# YOTSUBA_AP_EM_ver_3_1.net
KiCad netlist of a schematic drawn in EAGLE
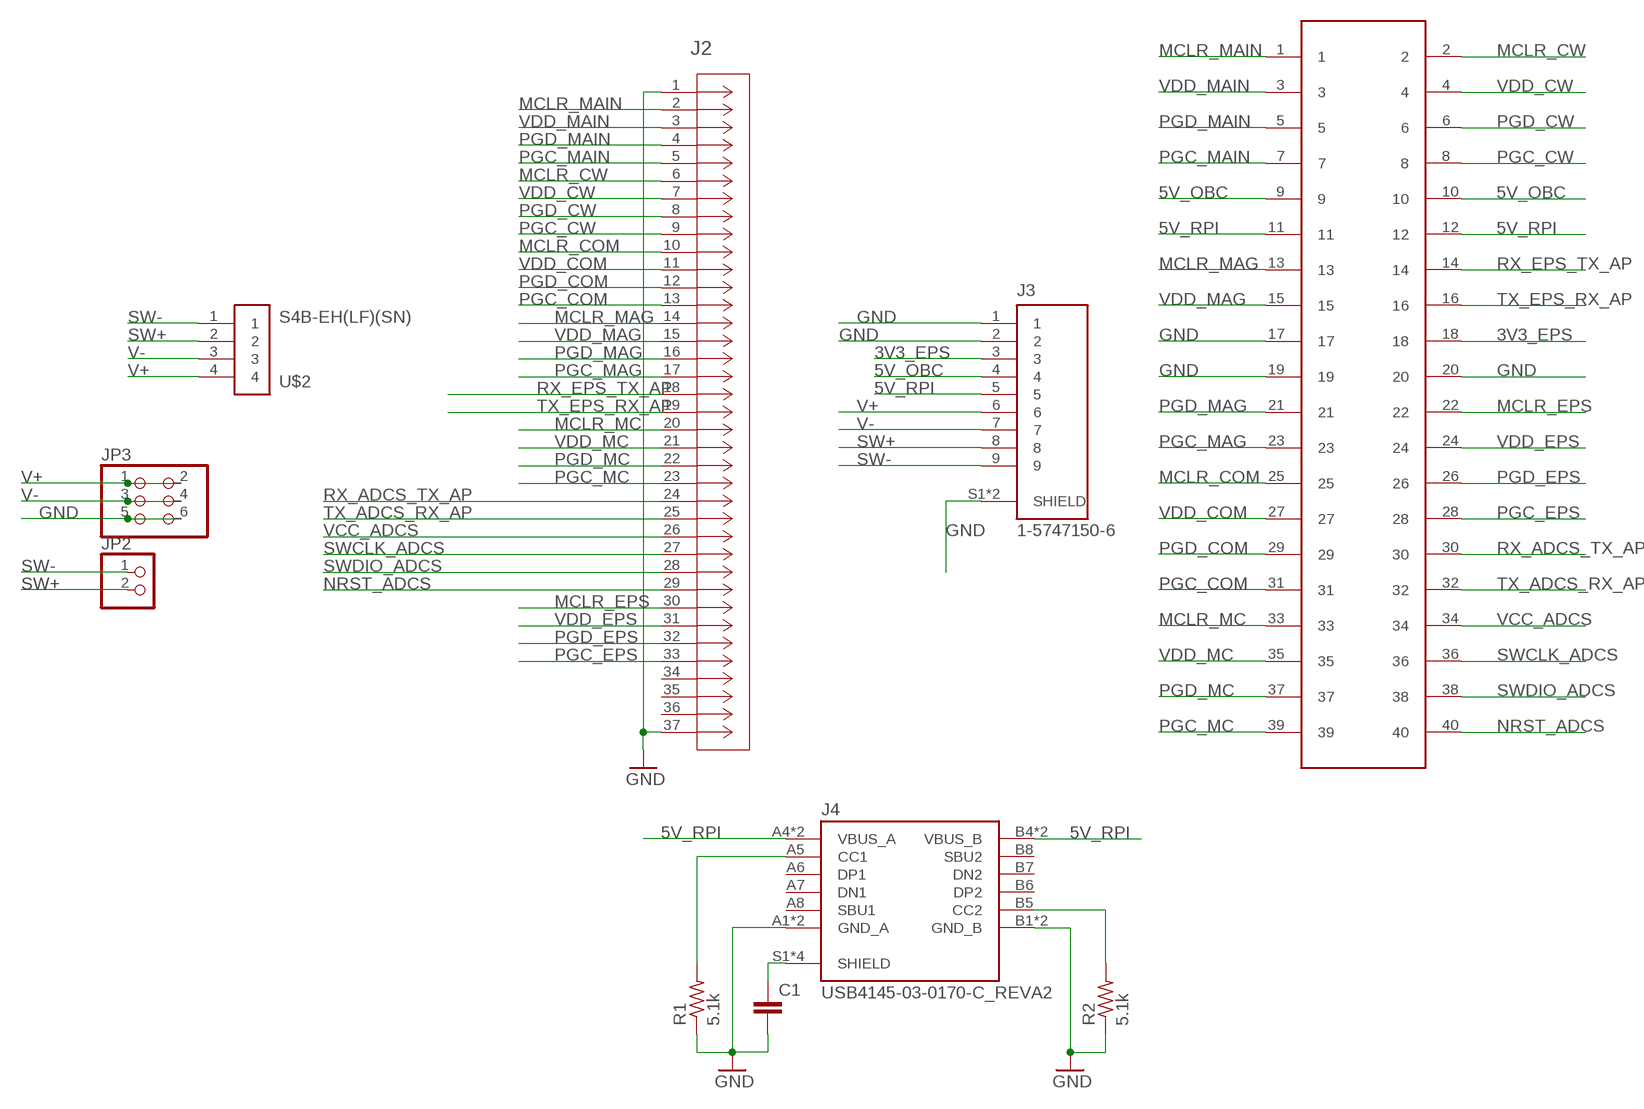
[diagram p0: schematic, sheet 1]

(export (version "E")
  (design (tool "Eeschema 10.0.6"))
  (components
    (comp (ref "C1")
      (value "C-EUC2012")
      (footprint "eagle-import:C2012")
      (libsource (lib "eagle-import") (part "C-EUC2012"))
    )
    (comp (ref "J2")
      (value "1-5747301-6")
      (footprint "eagle-import:CONN_1-5747301-6_TYC")
      (fields (field (name "COPYRIGHT") "Copyright (C) 2023 Ultra Librarian. All rights reserved."))
      (libsource (lib "eagle-import") (part "1-5747301-6"))
    )
    (comp (ref "J3")
      (value "1-5747150-6")
      (footprint "eagle-import:TE_1-5747150-6")
      (fields (field (name "MF") "TE Connectivity"))
      (libsource (lib "eagle-import") (part "1-5747150-6"))
    )
    (comp (ref "J4")
      (value "USB4145-03-0170-C_REVA2")
      (footprint "eagle-import:GCT_USB4145-03-0170-C_REVA2")
      (fields (field (name "MF") "Global Connector Technology") (field (name "MP") "USB4145-03-0170-C"))
      (libsource (lib "eagle-import") (part "USB4145-03-0170-C_REVA2"))
    )
    (comp (ref "JP2")
      (value "PINHD-1X2")
      (footprint "eagle-import:1X02")
      (libsource (lib "eagle-import") (part "PINHD-1X2"))
    )
    (comp (ref "JP3")
      (value "PINHD-2X3")
      (footprint "eagle-import:2X03")
      (libsource (lib "eagle-import") (part "PINHD-2X3"))
    )
    (comp (ref "R1")
      (value "5.1k")
      (footprint "eagle-import:R0805")
      (libsource (lib "eagle-import") (part "R-US_R0805"))
    )
    (comp (ref "R2")
      (value "5.1k")
      (footprint "eagle-import:R0805")
      (libsource (lib "eagle-import") (part "R-US_R0805"))
    )
    (comp (ref "U$1")
      (value "M50-3902042")
      (footprint "eagle-import:M50-3902042")
      (libsource (lib "eagle-import") (part "M50-3902042"))
    )
    (comp (ref "U$2")
      (value "S4B-EH(LF)(SN)")
      (footprint "eagle-import:JST_S4B-EH(LF)(SN)")
      (fields (field (name "MF") "JST Sales"))
      (libsource (lib "eagle-import") (part "S4B-EH(LF)(SN)"))
    )
  )
  (nets
    (net (code "1") (name "/3V3_EPS") (class "Default")
      (node (ref "J3") (pin "3") (pinfunction "3_3") (pintype "passive"))
      (node (ref "U$1") (pin "18") (pinfunction "18_18") (pintype "bidirectional"))
    )
    (net (code "2") (name "/5V_OBC") (class "Default")
      (node (ref "J3") (pin "4") (pinfunction "4_4") (pintype "passive"))
      (node (ref "U$1") (pin "10") (pinfunction "10_10") (pintype "bidirectional"))
      (node (ref "U$1") (pin "9") (pinfunction "9_9") (pintype "bidirectional"))
    )
    (net (code "3") (name "/5V_RPI") (class "Default")
      (node (ref "J3") (pin "5") (pinfunction "5_5") (pintype "passive"))
      (node (ref "J4") (pin "A4") (pinfunction "VBUS_A_A4") (pintype "power_in"))
      (node (ref "J4") (pin "A9") (pinfunction "VBUS_A_A9") (pintype "power_in"))
      (node (ref "J4") (pin "B4") (pinfunction "VBUS_B_B4") (pintype "power_in"))
      (node (ref "J4") (pin "B9") (pinfunction "VBUS_B_B9") (pintype "power_in"))
      (node (ref "U$1") (pin "11") (pinfunction "11_11") (pintype "bidirectional"))
      (node (ref "U$1") (pin "12") (pinfunction "12_12") (pintype "bidirectional"))
    )
    (net (code "4") (name "/MCLR_COM") (class "Default")
      (node (ref "J2") (pin "10") (pinfunction "10_10") (pintype "passive"))
      (node (ref "U$1") (pin "25") (pinfunction "25_25") (pintype "bidirectional"))
    )
    (net (code "5") (name "/MCLR_CW") (class "Default")
      (node (ref "J2") (pin "6") (pinfunction "6_6") (pintype "passive"))
      (node (ref "U$1") (pin "2") (pinfunction "2_2") (pintype "bidirectional"))
    )
    (net (code "6") (name "/MCLR_EPS") (class "Default")
      (node (ref "J2") (pin "30") (pinfunction "30_30") (pintype "passive"))
      (node (ref "U$1") (pin "22") (pinfunction "22_22") (pintype "bidirectional"))
    )
    (net (code "7") (name "/MCLR_MAG") (class "Default")
      (node (ref "J2") (pin "14") (pinfunction "14_14") (pintype "passive"))
      (node (ref "U$1") (pin "13") (pinfunction "13_13") (pintype "bidirectional"))
    )
    (net (code "8") (name "/MCLR_MAIN") (class "Default")
      (node (ref "J2") (pin "2") (pinfunction "2_2") (pintype "passive"))
      (node (ref "U$1") (pin "1") (pinfunction "1_1") (pintype "bidirectional"))
    )
    (net (code "9") (name "/MCLR_MC") (class "Default")
      (node (ref "J2") (pin "20") (pinfunction "20_20") (pintype "passive"))
      (node (ref "U$1") (pin "33") (pinfunction "33_33") (pintype "bidirectional"))
    )
    (net (code "10") (name "/NRST_ADCS") (class "Default")
      (node (ref "J2") (pin "29") (pinfunction "29_29") (pintype "passive"))
      (node (ref "U$1") (pin "40") (pinfunction "40_40") (pintype "bidirectional"))
    )
    (net (code "11") (name "/PGC_COM") (class "Default")
      (node (ref "J2") (pin "13") (pinfunction "13_13") (pintype "passive"))
      (node (ref "U$1") (pin "31") (pinfunction "31_31") (pintype "bidirectional"))
    )
    (net (code "12") (name "/PGC_CW") (class "Default")
      (node (ref "J2") (pin "9") (pinfunction "9_9") (pintype "passive"))
      (node (ref "U$1") (pin "8") (pinfunction "8_8") (pintype "bidirectional"))
    )
    (net (code "13") (name "/PGC_EPS") (class "Default")
      (node (ref "J2") (pin "33") (pinfunction "33_33") (pintype "passive"))
      (node (ref "U$1") (pin "28") (pinfunction "28_28") (pintype "bidirectional"))
    )
    (net (code "14") (name "/PGC_MAG") (class "Default")
      (node (ref "J2") (pin "17") (pinfunction "17_17") (pintype "passive"))
      (node (ref "U$1") (pin "23") (pinfunction "23_23") (pintype "bidirectional"))
    )
    (net (code "15") (name "/PGC_MAIN") (class "Default")
      (node (ref "J2") (pin "5") (pinfunction "5_5") (pintype "passive"))
      (node (ref "U$1") (pin "7") (pinfunction "7_7") (pintype "bidirectional"))
    )
    (net (code "16") (name "/PGC_MC") (class "Default")
      (node (ref "J2") (pin "23") (pinfunction "23_23") (pintype "passive"))
      (node (ref "U$1") (pin "39") (pinfunction "39_39") (pintype "bidirectional"))
    )
    (net (code "17") (name "/PGD_COM") (class "Default")
      (node (ref "J2") (pin "12") (pinfunction "12_12") (pintype "passive"))
      (node (ref "U$1") (pin "29") (pinfunction "29_29") (pintype "bidirectional"))
    )
    (net (code "18") (name "/PGD_CW") (class "Default")
      (node (ref "J2") (pin "8") (pinfunction "8_8") (pintype "passive"))
      (node (ref "U$1") (pin "6") (pinfunction "6_6") (pintype "bidirectional"))
    )
    (net (code "19") (name "/PGD_EPS") (class "Default")
      (node (ref "J2") (pin "32") (pinfunction "32_32") (pintype "passive"))
      (node (ref "U$1") (pin "26") (pinfunction "26_26") (pintype "bidirectional"))
    )
    (net (code "20") (name "/PGD_MAG") (class "Default")
      (node (ref "J2") (pin "16") (pinfunction "16_16") (pintype "passive"))
      (node (ref "U$1") (pin "21") (pinfunction "21_21") (pintype "bidirectional"))
    )
    (net (code "21") (name "/PGD_MAIN") (class "Default")
      (node (ref "J2") (pin "4") (pinfunction "4_4") (pintype "passive"))
      (node (ref "U$1") (pin "5") (pinfunction "5_5") (pintype "bidirectional"))
    )
    (net (code "22") (name "/PGD_MC") (class "Default")
      (node (ref "J2") (pin "22") (pinfunction "22_22") (pintype "passive"))
      (node (ref "U$1") (pin "37") (pinfunction "37_37") (pintype "bidirectional"))
    )
    (net (code "23") (name "/RX_ADCS_TX_AP") (class "Default")
      (node (ref "J2") (pin "24") (pinfunction "24_24") (pintype "passive"))
      (node (ref "U$1") (pin "30") (pinfunction "30_30") (pintype "bidirectional"))
    )
    (net (code "24") (name "/RX_EPS_TX_AP") (class "Default")
      (node (ref "J2") (pin "18") (pinfunction "18_18") (pintype "passive"))
      (node (ref "U$1") (pin "14") (pinfunction "14_14") (pintype "bidirectional"))
    )
    (net (code "25") (name "/SW+") (class "Default")
      (node (ref "J3") (pin "8") (pinfunction "8_8") (pintype "passive"))
      (node (ref "JP2") (pin "2") (pinfunction "2_2") (pintype "passive"))
      (node (ref "U$2") (pin "2") (pinfunction "2_2") (pintype "passive"))
    )
    (net (code "26") (name "/SW-") (class "Default")
      (node (ref "J3") (pin "9") (pinfunction "9_9") (pintype "passive"))
      (node (ref "JP2") (pin "1") (pinfunction "1_1") (pintype "passive"))
      (node (ref "U$2") (pin "1") (pinfunction "1_1") (pintype "passive"))
    )
    (net (code "27") (name "/SWCLK_ADCS") (class "Default")
      (node (ref "J2") (pin "27") (pinfunction "27_27") (pintype "passive"))
      (node (ref "U$1") (pin "36") (pinfunction "36_36") (pintype "bidirectional"))
    )
    (net (code "28") (name "/SWDIO_ADCS") (class "Default")
      (node (ref "J2") (pin "28") (pinfunction "28_28") (pintype "passive"))
      (node (ref "U$1") (pin "38") (pinfunction "38_38") (pintype "bidirectional"))
    )
    (net (code "29") (name "/TX_ADCS_RX_AP") (class "Default")
      (node (ref "J2") (pin "25") (pinfunction "25_25") (pintype "passive"))
      (node (ref "U$1") (pin "32") (pinfunction "32_32") (pintype "bidirectional"))
    )
    (net (code "30") (name "/TX_EPS_RX_AP") (class "Default")
      (node (ref "J2") (pin "19") (pinfunction "19_19") (pintype "passive"))
      (node (ref "U$1") (pin "16") (pinfunction "16_16") (pintype "bidirectional"))
    )
    (net (code "31") (name "/V+") (class "Default")
      (node (ref "J3") (pin "6") (pinfunction "6_6") (pintype "passive"))
      (node (ref "JP3") (pin "1") (pinfunction "1_1") (pintype "passive"))
      (node (ref "JP3") (pin "2") (pinfunction "2_2") (pintype "passive"))
      (node (ref "U$2") (pin "4") (pinfunction "4_4") (pintype "passive"))
    )
    (net (code "32") (name "/V-") (class "Default")
      (node (ref "J3") (pin "7") (pinfunction "7_7") (pintype "passive"))
      (node (ref "JP3") (pin "3") (pinfunction "3_3") (pintype "passive"))
      (node (ref "JP3") (pin "4") (pinfunction "4_4") (pintype "passive"))
      (node (ref "U$2") (pin "3") (pinfunction "3_3") (pintype "passive"))
    )
    (net (code "33") (name "/VCC_ADCS") (class "Default")
      (node (ref "J2") (pin "26") (pinfunction "26_26") (pintype "passive"))
      (node (ref "U$1") (pin "34") (pinfunction "34_34") (pintype "bidirectional"))
    )
    (net (code "34") (name "/VDD_COM") (class "Default")
      (node (ref "J2") (pin "11") (pinfunction "11_11") (pintype "passive"))
      (node (ref "U$1") (pin "27") (pinfunction "27_27") (pintype "bidirectional"))
    )
    (net (code "35") (name "/VDD_CW") (class "Default")
      (node (ref "J2") (pin "7") (pinfunction "7_7") (pintype "passive"))
      (node (ref "U$1") (pin "4") (pinfunction "4_4") (pintype "bidirectional"))
    )
    (net (code "36") (name "/VDD_EPS") (class "Default")
      (node (ref "J2") (pin "31") (pinfunction "31_31") (pintype "passive"))
      (node (ref "U$1") (pin "24") (pinfunction "24_24") (pintype "bidirectional"))
    )
    (net (code "37") (name "/VDD_MAG") (class "Default")
      (node (ref "J2") (pin "15") (pinfunction "15_15") (pintype "passive"))
      (node (ref "U$1") (pin "15") (pinfunction "15_15") (pintype "bidirectional"))
    )
    (net (code "38") (name "/VDD_MAIN") (class "Default")
      (node (ref "J2") (pin "3") (pinfunction "3_3") (pintype "passive"))
      (node (ref "U$1") (pin "3") (pinfunction "3_3") (pintype "bidirectional"))
    )
    (net (code "39") (name "/VDD_MC") (class "Default")
      (node (ref "J2") (pin "21") (pinfunction "21_21") (pintype "passive"))
      (node (ref "U$1") (pin "35") (pinfunction "35_35") (pintype "bidirectional"))
    )
    (net (code "40") (name "GND") (class "Default")
      (node (ref "C1") (pin "2") (pinfunction "2_2") (pintype "passive"))
      (node (ref "J2") (pin "1") (pinfunction "1_1") (pintype "passive"))
      (node (ref "J2") (pin "37") (pinfunction "37_37") (pintype "passive"))
      (node (ref "J3") (pin "1") (pinfunction "1_1") (pintype "passive"))
      (node (ref "J3") (pin "2") (pinfunction "2_2") (pintype "passive"))
      (node (ref "J3") (pin "S1") (pinfunction "SHIELD_S1") (pintype "passive"))
      (node (ref "J3") (pin "S2") (pinfunction "SHIELD_S2") (pintype "passive"))
      (node (ref "J4") (pin "A1") (pinfunction "GND_A_A1") (pintype "power_in"))
      (node (ref "J4") (pin "A12") (pinfunction "GND_A_A12") (pintype "power_in"))
      (node (ref "J4") (pin "B1") (pinfunction "GND_B_B1") (pintype "power_in"))
      (node (ref "J4") (pin "B12") (pinfunction "GND_B_B12") (pintype "power_in"))
      (node (ref "JP3") (pin "5") (pinfunction "5_5") (pintype "passive"))
      (node (ref "JP3") (pin "6") (pinfunction "6_6") (pintype "passive"))
      (node (ref "R1") (pin "1") (pinfunction "1_1") (pintype "passive"))
      (node (ref "R2") (pin "1") (pinfunction "1_1") (pintype "passive"))
      (node (ref "U$1") (pin "17") (pinfunction "17_17") (pintype "bidirectional"))
      (node (ref "U$1") (pin "19") (pinfunction "19_19") (pintype "bidirectional"))
      (node (ref "U$1") (pin "20") (pinfunction "20_20") (pintype "bidirectional"))
    )
    (net (code "41") (name "Net-(C1-Pad1)") (class "Default")
      (node (ref "C1") (pin "1") (pinfunction "1_1") (pintype "passive"))
      (node (ref "J4") (pin "S1") (pinfunction "SHIELD_S1") (pintype "passive"))
      (node (ref "J4") (pin "S2") (pinfunction "SHIELD_S2") (pintype "passive"))
      (node (ref "J4") (pin "S3") (pinfunction "SHIELD_S3") (pintype "passive"))
      (node (ref "J4") (pin "S4") (pinfunction "SHIELD_S4") (pintype "passive"))
    )
    (net (code "42") (name "Net-(J4-CC1)") (class "Default")
      (node (ref "J4") (pin "A5") (pinfunction "CC1_A5") (pintype "bidirectional"))
      (node (ref "R1") (pin "2") (pinfunction "2_2") (pintype "passive"))
    )
    (net (code "43") (name "Net-(J4-CC2)") (class "Default")
      (node (ref "J4") (pin "B5") (pinfunction "CC2_B5") (pintype "bidirectional"))
      (node (ref "R2") (pin "2") (pinfunction "2_2") (pintype "passive"))
    )
    (net (code "44") (name "unconnected-(J2-Pad34)") (class "Default")
      (node (ref "J2") (pin "34") (pinfunction "34_34") (pintype "passive"))
    )
    (net (code "45") (name "unconnected-(J2-Pad35)") (class "Default")
      (node (ref "J2") (pin "35") (pinfunction "35_35") (pintype "passive"))
    )
    (net (code "46") (name "unconnected-(J2-Pad36)") (class "Default")
      (node (ref "J2") (pin "36") (pinfunction "36_36") (pintype "passive"))
    )
    (net (code "47") (name "unconnected-(J4-DN1-PadA7)") (class "Default")
      (node (ref "J4") (pin "A7") (pinfunction "DN1_A7") (pintype "bidirectional"))
    )
    (net (code "48") (name "unconnected-(J4-DN2-PadB7)") (class "Default")
      (node (ref "J4") (pin "B7") (pinfunction "DN2_B7") (pintype "bidirectional"))
    )
    (net (code "49") (name "unconnected-(J4-DP1-PadA6)") (class "Default")
      (node (ref "J4") (pin "A6") (pinfunction "DP1_A6") (pintype "bidirectional"))
    )
    (net (code "50") (name "unconnected-(J4-DP2-PadB6)") (class "Default")
      (node (ref "J4") (pin "B6") (pinfunction "DP2_B6") (pintype "bidirectional"))
    )
    (net (code "51") (name "unconnected-(J4-SBU1-PadA8)") (class "Default")
      (node (ref "J4") (pin "A8") (pinfunction "SBU1_A8") (pintype "bidirectional"))
    )
    (net (code "52") (name "unconnected-(J4-SBU2-PadB8)") (class "Default")
      (node (ref "J4") (pin "B8") (pinfunction "SBU2_B8") (pintype "bidirectional"))
    )
  )
)
